# rat.net
KiCad netlist of a schematic drawn in EAGLE
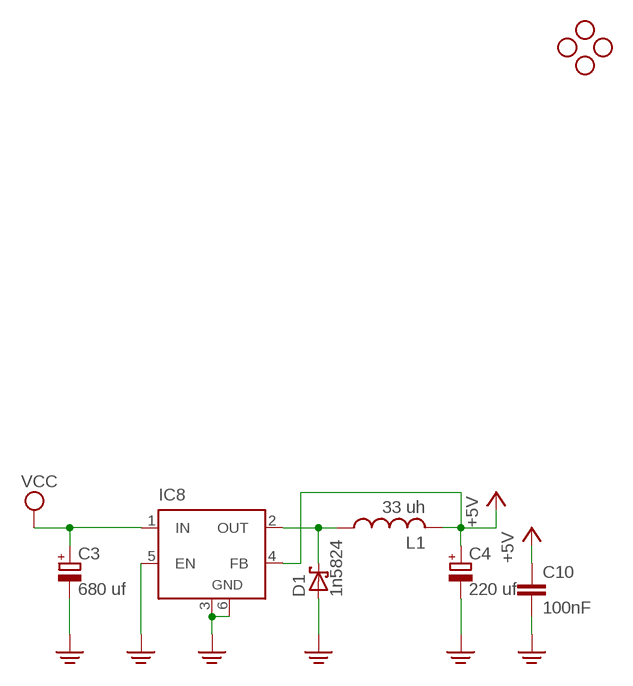
[diagram p0: schematic, sheet 1, part 1 of 2]
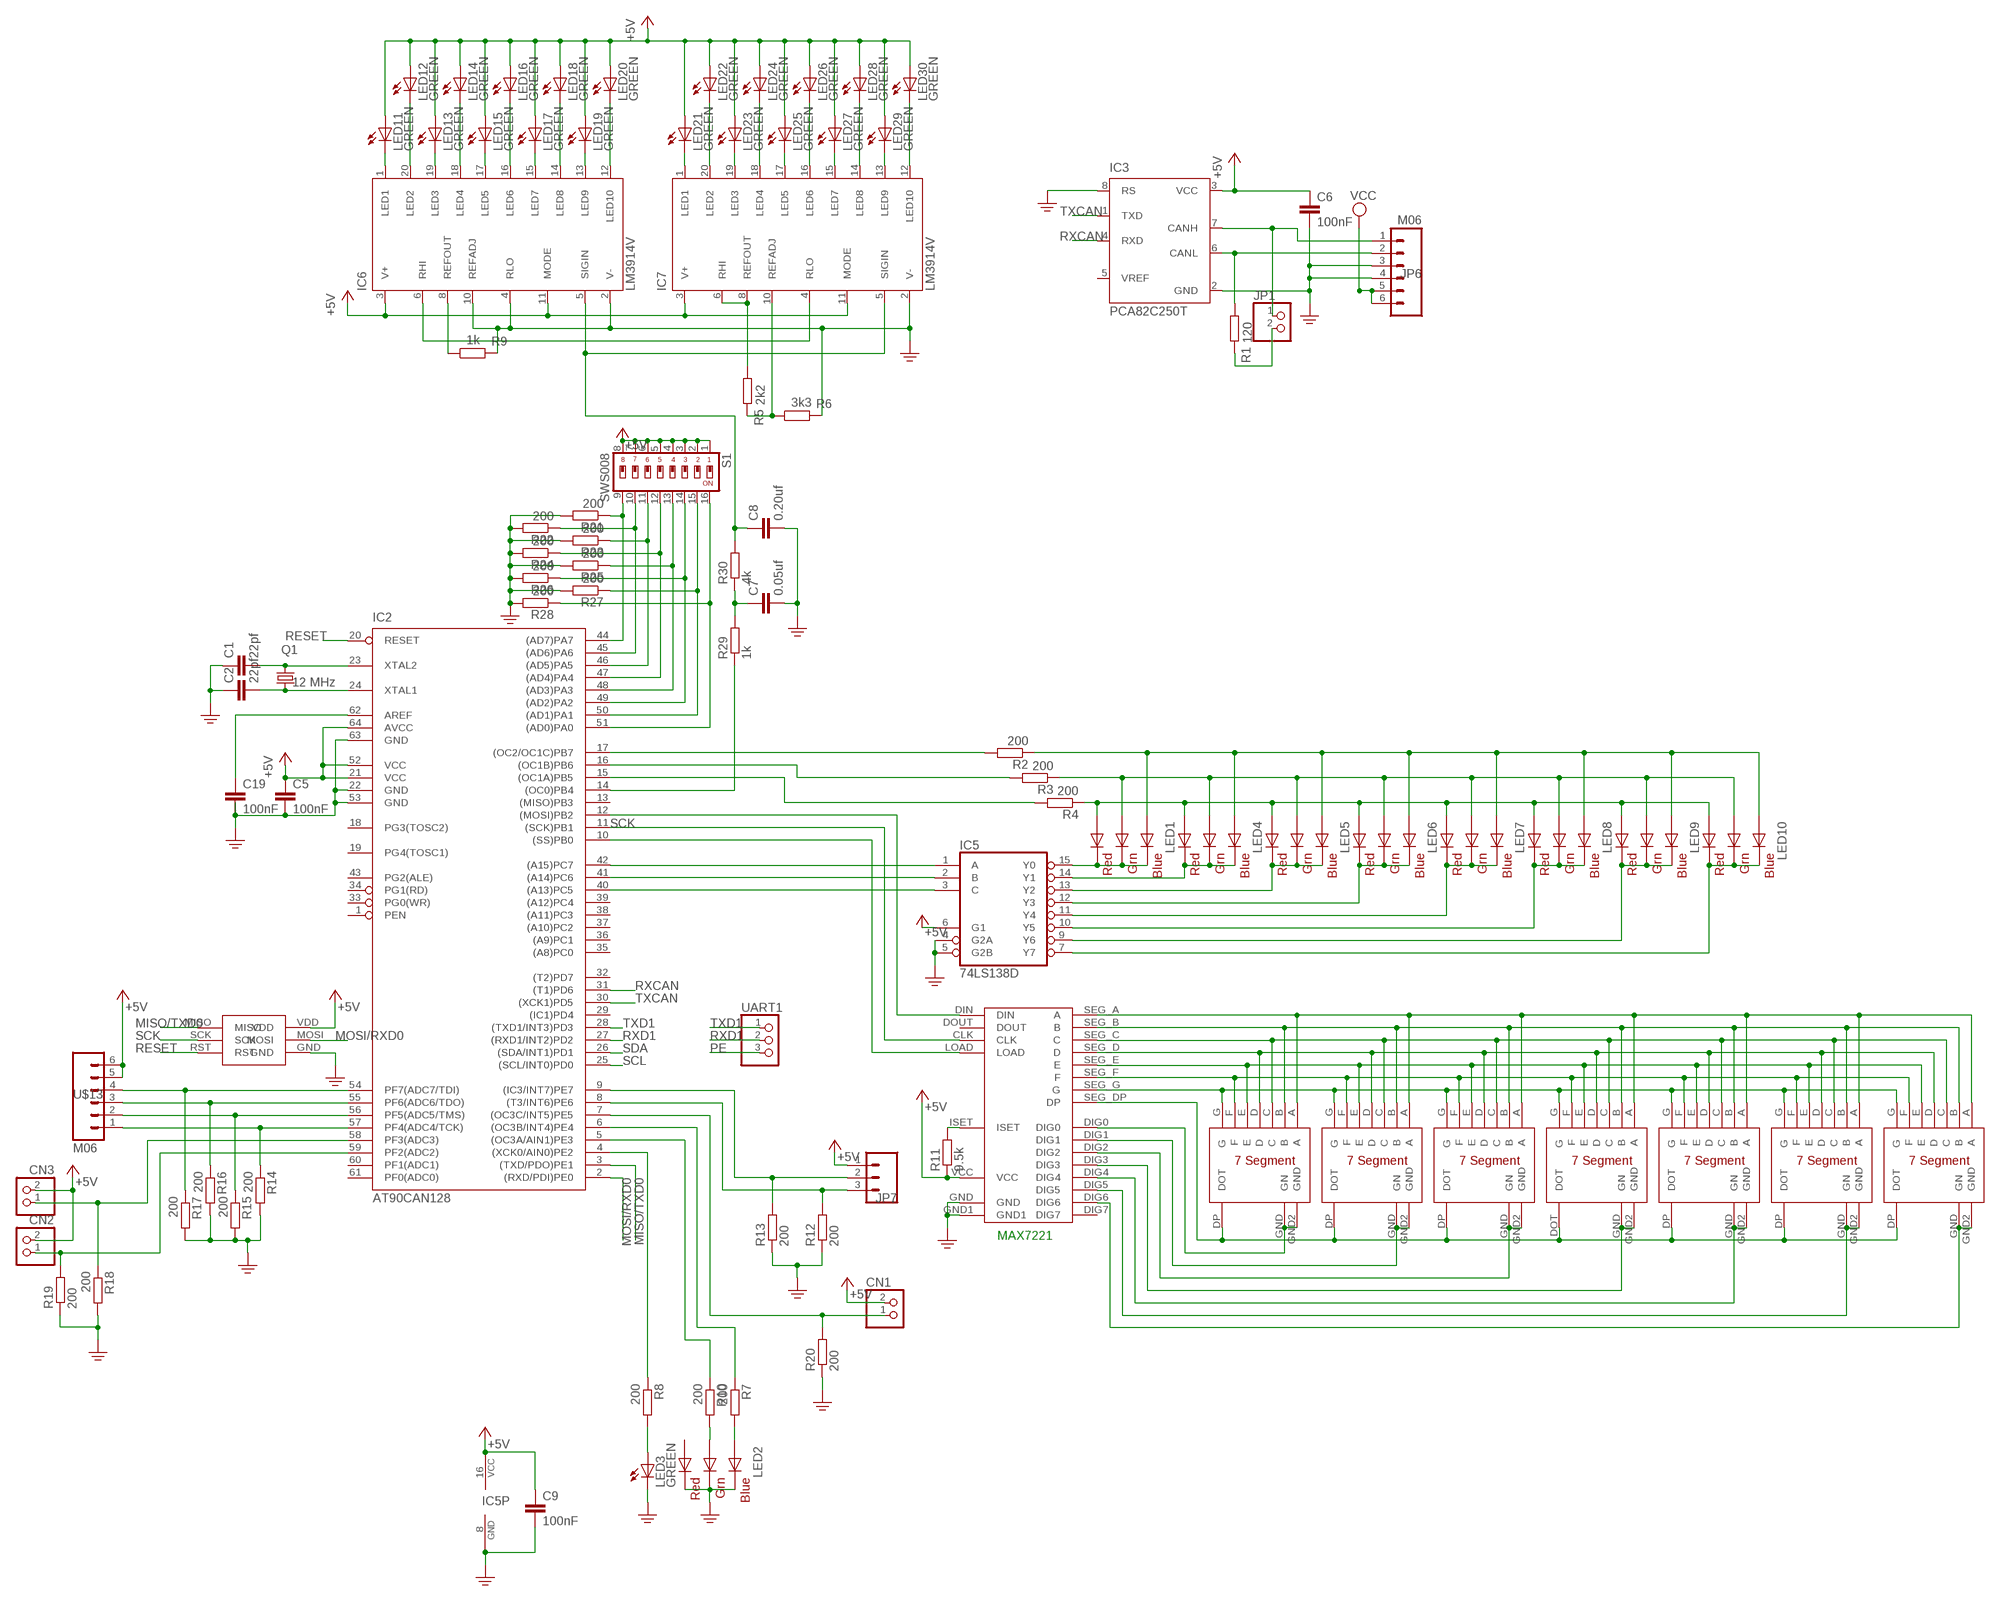
[diagram p1: schematic, sheet 1, part 2 of 2]

(export (version "E")
  (design (tool "Eeschema 10.0.6"))
  (components
    (comp (ref "C1")
      (value "22pf")
      (footprint "eagle-import:C0603K")
      (libsource (lib "eagle-import") (part "C-EUC0603K"))
    )
    (comp (ref "C2")
      (value "22pf")
      (footprint "eagle-import:C0603K")
      (libsource (lib "eagle-import") (part "C-EUC0603K"))
    )
    (comp (ref "C3")
      (value "680 uf")
      (footprint "eagle-import:E5-10,5")
      (libsource (lib "eagle-import") (part "CPOL-EUE5-10.5"))
    )
    (comp (ref "C4")
      (value "220 uf")
      (footprint "eagle-import:E2,5-7")
      (libsource (lib "eagle-import") (part "CPOL-EUE2.5-7"))
    )
    (comp (ref "C5")
      (value "100nF")
      (footprint "eagle-import:C0603K")
      (libsource (lib "eagle-import") (part "C-EUC0603K"))
    )
    (comp (ref "C6")
      (value "100nF")
      (footprint "eagle-import:C0603K")
      (libsource (lib "eagle-import") (part "C-EUC0603K"))
    )
    (comp (ref "C7")
      (value "0.05uf")
      (footprint "eagle-import:C0603K")
      (libsource (lib "eagle-import") (part "C-EUC0603K"))
    )
    (comp (ref "C8")
      (value "0.20uf")
      (footprint "eagle-import:C0603K")
      (libsource (lib "eagle-import") (part "C-EUC0603K"))
    )
    (comp (ref "C9")
      (value "100nF")
      (footprint "eagle-import:C0603K")
      (libsource (lib "eagle-import") (part "C-EUC0603K"))
    )
    (comp (ref "C10")
      (value "100nF")
      (footprint "eagle-import:C0603K")
      (libsource (lib "eagle-import") (part "C-EUC0603K"))
    )
    (comp (ref "C19")
      (value "100nF")
      (footprint "eagle-import:C0603K")
      (libsource (lib "eagle-import") (part "C-EUC0603K"))
    )
    (comp (ref "CN1")
      (value "JST_2PIN-SMT-RA")
      (footprint "eagle-import:JST-PH-2-SMT-RA")
      (libsource (lib "eagle-import") (part "JST_2PIN-SMT-RA"))
    )
    (comp (ref "CN2")
      (value "JST_2PIN-SMT-RA")
      (footprint "eagle-import:JST-PH-2-SMT-RA")
      (libsource (lib "eagle-import") (part "JST_2PIN-SMT-RA"))
    )
    (comp (ref "CN3")
      (value "JST_2PIN-SMT-RA")
      (footprint "eagle-import:JST-PH-2-SMT-RA")
      (libsource (lib "eagle-import") (part "JST_2PIN-SMT-RA"))
    )
    (comp (ref "D1")
      (value "1n5824")
      (footprint "eagle-import:P6T15")
      (libsource (lib "eagle-import") (part "SCHOTTKY-DIODEP6T15"))
    )
    (comp (ref "IC2")
      (value "AT90CAN128")
      (footprint "eagle-import:TQFP64")
      (fields (field (name "MPN") "ATMEGA128-16AU"))
      (libsource (lib "eagle-import") (part "MEGA128-A"))
    )
    (comp (ref "IC3")
      (value "PCA82C250T")
      (footprint "eagle-import:SO8")
      (libsource (lib "eagle-import") (part "PCA82C250T"))
    )
    (comp (ref "IC5")
      (value "74LS138D")
      (footprint "eagle-import:SO16")
      (libsource (lib "eagle-import") (part "74138DLS"))
    )
    (comp (ref "IC6")
      (value "LM3914V")
      (footprint "eagle-import:PLCC20S")
      (libsource (lib "eagle-import") (part "LM391V4"))
    )
    (comp (ref "IC7")
      (value "LM3914V")
      (footprint "eagle-import:PLCC20S")
      (libsource (lib "eagle-import") (part "LM391V4"))
    )
    (comp (ref "IC8")
      (value "LM2596S")
      (footprint "eagle-import:TO263-5")
      (libsource (lib "eagle-import") (part "LM2596S"))
    )
    (comp (ref "JP1")
      (value "PINHD-1X2")
      (footprint "eagle-import:1X02")
      (libsource (lib "eagle-import") (part "PINHD-1X2"))
    )
    (comp (ref "JP2")
      (value "STAND-OFF")
      (footprint "eagle-import:STAND-OFF")
      (libsource (lib "eagle-import") (part "STAND-OFF"))
    )
    (comp (ref "JP3")
      (value "STAND-OFF")
      (footprint "eagle-import:STAND-OFF")
      (libsource (lib "eagle-import") (part "STAND-OFF"))
    )
    (comp (ref "JP4")
      (value "STAND-OFF")
      (footprint "eagle-import:STAND-OFF")
      (libsource (lib "eagle-import") (part "STAND-OFF"))
    )
    (comp (ref "JP5")
      (value "STAND-OFF")
      (footprint "eagle-import:STAND-OFF")
      (libsource (lib "eagle-import") (part "STAND-OFF"))
    )
    (comp (ref "JP6")
      (value "M06")
      (footprint "eagle-import:S6B_PH")
      (libsource (lib "eagle-import") (part "M06"))
    )
    (comp (ref "JP7")
      (value "M03")
      (footprint "eagle-import:S3B-PH")
      (libsource (lib "eagle-import") (part "M03"))
    )
    (comp (ref "L1")
      (value "33 uh")
      (footprint "eagle-import:TFI0410")
      (libsource (lib "eagle-import") (part "L-USTFI0410"))
    )
    (comp (ref "LED1")
      (value "RGBLED5050")
      (footprint "eagle-import:RGBLED5050")
      (libsource (lib "eagle-import") (part "RGBLED5050"))
    )
    (comp (ref "LED2")
      (value "RGBLED5050")
      (footprint "eagle-import:RGBLED5050")
      (libsource (lib "eagle-import") (part "RGBLED5050"))
    )
    (comp (ref "LED3")
      (value "GREEN")
      (footprint "eagle-import:1206")
      (libsource (lib "eagle-import") (part "LEDSMT1206"))
    )
    (comp (ref "LED4")
      (value "RGBLED5050")
      (footprint "eagle-import:RGBLED5050")
      (libsource (lib "eagle-import") (part "RGBLED5050"))
    )
    (comp (ref "LED5")
      (value "RGBLED5050")
      (footprint "eagle-import:RGBLED5050")
      (libsource (lib "eagle-import") (part "RGBLED5050"))
    )
    (comp (ref "LED6")
      (value "RGBLED5050")
      (footprint "eagle-import:RGBLED5050")
      (libsource (lib "eagle-import") (part "RGBLED5050"))
    )
    (comp (ref "LED7")
      (value "RGBLED5050")
      (footprint "eagle-import:RGBLED5050")
      (libsource (lib "eagle-import") (part "RGBLED5050"))
    )
    (comp (ref "LED8")
      (value "RGBLED5050")
      (footprint "eagle-import:RGBLED5050")
      (libsource (lib "eagle-import") (part "RGBLED5050"))
    )
    (comp (ref "LED9")
      (value "RGBLED5050")
      (footprint "eagle-import:RGBLED5050")
      (libsource (lib "eagle-import") (part "RGBLED5050"))
    )
    (comp (ref "LED10")
      (value "RGBLED5050")
      (footprint "eagle-import:RGBLED5050")
      (libsource (lib "eagle-import") (part "RGBLED5050"))
    )
    (comp (ref "LED11")
      (value "GREEN")
      (footprint "eagle-import:1206")
      (libsource (lib "eagle-import") (part "LEDSMT1206"))
    )
    (comp (ref "LED12")
      (value "GREEN")
      (footprint "eagle-import:1206")
      (libsource (lib "eagle-import") (part "LEDSMT1206"))
    )
    (comp (ref "LED13")
      (value "GREEN")
      (footprint "eagle-import:1206")
      (libsource (lib "eagle-import") (part "LEDSMT1206"))
    )
    (comp (ref "LED14")
      (value "GREEN")
      (footprint "eagle-import:1206")
      (libsource (lib "eagle-import") (part "LEDSMT1206"))
    )
    (comp (ref "LED15")
      (value "GREEN")
      (footprint "eagle-import:1206")
      (libsource (lib "eagle-import") (part "LEDSMT1206"))
    )
    (comp (ref "LED16")
      (value "GREEN")
      (footprint "eagle-import:1206")
      (libsource (lib "eagle-import") (part "LEDSMT1206"))
    )
    (comp (ref "LED17")
      (value "GREEN")
      (footprint "eagle-import:1206")
      (libsource (lib "eagle-import") (part "LEDSMT1206"))
    )
    (comp (ref "LED18")
      (value "GREEN")
      (footprint "eagle-import:1206")
      (libsource (lib "eagle-import") (part "LEDSMT1206"))
    )
    (comp (ref "LED19")
      (value "GREEN")
      (footprint "eagle-import:1206")
      (libsource (lib "eagle-import") (part "LEDSMT1206"))
    )
    (comp (ref "LED20")
      (value "GREEN")
      (footprint "eagle-import:1206")
      (libsource (lib "eagle-import") (part "LEDSMT1206"))
    )
    (comp (ref "LED21")
      (value "GREEN")
      (footprint "eagle-import:1206")
      (libsource (lib "eagle-import") (part "LEDSMT1206"))
    )
    (comp (ref "LED22")
      (value "GREEN")
      (footprint "eagle-import:1206")
      (libsource (lib "eagle-import") (part "LEDSMT1206"))
    )
    (comp (ref "LED23")
      (value "GREEN")
      (footprint "eagle-import:1206")
      (libsource (lib "eagle-import") (part "LEDSMT1206"))
    )
    (comp (ref "LED24")
      (value "GREEN")
      (footprint "eagle-import:1206")
      (libsource (lib "eagle-import") (part "LEDSMT1206"))
    )
    (comp (ref "LED25")
      (value "GREEN")
      (footprint "eagle-import:1206")
      (libsource (lib "eagle-import") (part "LEDSMT1206"))
    )
    (comp (ref "LED26")
      (value "GREEN")
      (footprint "eagle-import:1206")
      (libsource (lib "eagle-import") (part "LEDSMT1206"))
    )
    (comp (ref "LED27")
      (value "GREEN")
      (footprint "eagle-import:1206")
      (libsource (lib "eagle-import") (part "LEDSMT1206"))
    )
    (comp (ref "LED28")
      (value "GREEN")
      (footprint "eagle-import:1206")
      (libsource (lib "eagle-import") (part "LEDSMT1206"))
    )
    (comp (ref "LED29")
      (value "GREEN")
      (footprint "eagle-import:1206")
      (libsource (lib "eagle-import") (part "LEDSMT1206"))
    )
    (comp (ref "LED30")
      (value "GREEN")
      (footprint "eagle-import:1206")
      (libsource (lib "eagle-import") (part "LEDSMT1206"))
    )
    (comp (ref "Q1")
      (value "12 MHz")
      (footprint "eagle-import:HC49U70")
      (libsource (lib "eagle-import") (part "CRYSTALHC49U70"))
    )
    (comp (ref "R1")
      (value "120")
      (footprint "eagle-import:R0603")
      (libsource (lib "eagle-import") (part "resistor_R-EU_R0603"))
    )
    (comp (ref "R2")
      (value "200")
      (footprint "eagle-import:R0603")
      (libsource (lib "eagle-import") (part "R-EU_R0603"))
    )
    (comp (ref "R3")
      (value "200")
      (footprint "eagle-import:R0603")
      (libsource (lib "eagle-import") (part "R-EU_R0603"))
    )
    (comp (ref "R4")
      (value "200")
      (footprint "eagle-import:R0603")
      (libsource (lib "eagle-import") (part "R-EU_R0603"))
    )
    (comp (ref "R5")
      (value "2k2")
      (footprint "eagle-import:R0603")
      (libsource (lib "eagle-import") (part "resistor_R-EU_R0603"))
    )
    (comp (ref "R6")
      (value "3k3")
      (footprint "eagle-import:R0603")
      (libsource (lib "eagle-import") (part "resistor_R-EU_R0603"))
    )
    (comp (ref "R7")
      (value "200")
      (footprint "eagle-import:R0603")
      (libsource (lib "eagle-import") (part "R-EU_R0603"))
    )
    (comp (ref "R8")
      (value "200")
      (footprint "eagle-import:R0603")
      (libsource (lib "eagle-import") (part "R-EU_R0603"))
    )
    (comp (ref "R9")
      (value "1k")
      (footprint "eagle-import:R0603")
      (libsource (lib "eagle-import") (part "resistor_R-EU_R0603"))
    )
    (comp (ref "R10")
      (value "200")
      (footprint "eagle-import:R0603")
      (libsource (lib "eagle-import") (part "R-EU_R0603"))
    )
    (comp (ref "R11")
      (value "9.5k")
      (footprint "eagle-import:R0603")
      (libsource (lib "eagle-import") (part "R-EU_R0603"))
    )
    (comp (ref "R12")
      (value "200")
      (footprint "eagle-import:R0603")
      (libsource (lib "eagle-import") (part "R-EU_R0603"))
    )
    (comp (ref "R13")
      (value "200")
      (footprint "eagle-import:R0603")
      (libsource (lib "eagle-import") (part "R-EU_R0603"))
    )
    (comp (ref "R14")
      (value "200")
      (footprint "eagle-import:R0603")
      (libsource (lib "eagle-import") (part "R-EU_R0603"))
    )
    (comp (ref "R15")
      (value "200")
      (footprint "eagle-import:R0603")
      (libsource (lib "eagle-import") (part "R-EU_R0603"))
    )
    (comp (ref "R16")
      (value "200")
      (footprint "eagle-import:R0603")
      (libsource (lib "eagle-import") (part "R-EU_R0603"))
    )
    (comp (ref "R17")
      (value "200")
      (footprint "eagle-import:R0603")
      (libsource (lib "eagle-import") (part "R-EU_R0603"))
    )
    (comp (ref "R18")
      (value "200")
      (footprint "eagle-import:R0603")
      (libsource (lib "eagle-import") (part "R-EU_R0603"))
    )
    (comp (ref "R19")
      (value "200")
      (footprint "eagle-import:R0603")
      (libsource (lib "eagle-import") (part "R-EU_R0603"))
    )
    (comp (ref "R20")
      (value "200")
      (footprint "eagle-import:R0603")
      (libsource (lib "eagle-import") (part "R-EU_R0603"))
    )
    (comp (ref "R21")
      (value "200")
      (footprint "eagle-import:R0603")
      (libsource (lib "eagle-import") (part "R-EU_R0603"))
    )
    (comp (ref "R22")
      (value "200")
      (footprint "eagle-import:R0603")
      (libsource (lib "eagle-import") (part "R-EU_R0603"))
    )
    (comp (ref "R23")
      (value "200")
      (footprint "eagle-import:R0603")
      (libsource (lib "eagle-import") (part "R-EU_R0603"))
    )
    (comp (ref "R24")
      (value "200")
      (footprint "eagle-import:R0603")
      (libsource (lib "eagle-import") (part "R-EU_R0603"))
    )
    (comp (ref "R25")
      (value "200")
      (footprint "eagle-import:R0603")
      (libsource (lib "eagle-import") (part "R-EU_R0603"))
    )
    (comp (ref "R26")
      (value "200")
      (footprint "eagle-import:R0603")
      (libsource (lib "eagle-import") (part "R-EU_R0603"))
    )
    (comp (ref "R27")
      (value "200")
      (footprint "eagle-import:R0603")
      (libsource (lib "eagle-import") (part "R-EU_R0603"))
    )
    (comp (ref "R28")
      (value "200")
      (footprint "eagle-import:R0603")
      (libsource (lib "eagle-import") (part "R-EU_R0603"))
    )
    (comp (ref "R29")
      (value "1k")
      (footprint "eagle-import:R0603")
      (libsource (lib "eagle-import") (part "R-EU_R0603"))
    )
    (comp (ref "R30")
      (value "4k")
      (footprint "eagle-import:R0603")
      (libsource (lib "eagle-import") (part "R-EU_R0603"))
    )
    (comp (ref "S1")
      (value "SWS008")
      (footprint "eagle-import:SMS-008")
      (libsource (lib "eagle-import") (part "SWS008"))
    )
    (comp (ref "U$2")
      (value "REDSEVENSEGMENT")
      (footprint "eagle-import:REDSEGMENT")
      (libsource (lib "eagle-import") (part "REDSEVENSEGMENT"))
    )
    (comp (ref "U$3")
      (value "REDSEVENSEGMENT")
      (footprint "eagle-import:REDSEGMENT")
      (libsource (lib "eagle-import") (part "REDSEVENSEGMENT"))
    )
    (comp (ref "U$4")
      (value "REDSEVENSEGMENT")
      (footprint "eagle-import:REDSEGMENT")
      (libsource (lib "eagle-import") (part "REDSEVENSEGMENT"))
    )
    (comp (ref "U$5")
      (value "BIGSEVENSEGMENT")
      (footprint "eagle-import:BIGSEVENSEGMENT")
      (libsource (lib "eagle-import") (part "BIGSEVENSEGMENT"))
    )
    (comp (ref "U$6")
      (value "REDSEVENSEGMENT")
      (footprint "eagle-import:REDSEGMENT")
      (libsource (lib "eagle-import") (part "REDSEVENSEGMENT"))
    )
    (comp (ref "U$7")
      (value "REDSEVENSEGMENT")
      (footprint "eagle-import:REDSEGMENT")
      (libsource (lib "eagle-import") (part "REDSEVENSEGMENT"))
    )
    (comp (ref "U$8")
      (value "REDSEVENSEGMENT")
      (footprint "eagle-import:REDSEGMENT")
      (libsource (lib "eagle-import") (part "REDSEVENSEGMENT"))
    )
    (comp (ref "U$9")
      (value "ISP-HEADER")
      (footprint "eagle-import:ISP-HEADER")
      (libsource (lib "eagle-import") (part "ISP-HEADER"))
    )
    (comp (ref "U$13")
      (value "M06")
      (footprint "eagle-import:S6B_PH")
      (libsource (lib "eagle-import") (part "M06"))
    )
    (comp (ref "U$14")
      (value "MAX7221-SMD")
      (footprint "eagle-import:MAX7221")
      (libsource (lib "eagle-import") (part "MAX7221-SMD"))
    )
    (comp (ref "UART1")
      (value "PINHD-1X3")
      (footprint "eagle-import:1X03")
      (libsource (lib "eagle-import") (part "PINHD-1X3"))
    )
  )
  (nets
    (net (code "1") (name "+5V") (class "Default")
      (node (ref "C10") (pin "1") (pinfunction "1_1") (pintype "passive"))
      (node (ref "C4") (pin "+") (pinfunction "+_+") (pintype "passive"))
      (node (ref "C5") (pin "1") (pinfunction "1_1") (pintype "passive"))
      (node (ref "C6") (pin "1") (pinfunction "1_1") (pintype "passive"))
      (node (ref "C9") (pin "1") (pinfunction "1_1") (pintype "passive"))
      (node (ref "CN1") (pin "2") (pinfunction "1_2") (pintype "passive"))
      (node (ref "CN2") (pin "2") (pinfunction "1_2") (pintype "passive"))
      (node (ref "CN3") (pin "2") (pinfunction "1_2") (pintype "passive"))
      (node (ref "IC2") (pin "21") (pinfunction "VCC_21") (pintype "power_in"))
      (node (ref "IC2") (pin "52") (pinfunction "VCC_52") (pintype "power_in"))
      (node (ref "IC2") (pin "64") (pinfunction "AVCC_64") (pintype "power_in"))
      (node (ref "IC3") (pin "3") (pinfunction "VCC_3") (pintype "power_in"))
      (node (ref "IC5") (pin "16") (pinfunction "VCC_16") (pintype "power_in"))
      (node (ref "IC5") (pin "6") (pinfunction "G1_6") (pintype "input"))
      (node (ref "IC6") (pin "11") (pinfunction "MODE_11") (pintype "input"))
      (node (ref "IC6") (pin "3") (pinfunction "V+_3") (pintype "power_in"))
      (node (ref "IC7") (pin "11") (pinfunction "MODE_11") (pintype "input"))
      (node (ref "IC7") (pin "3") (pinfunction "V+_3") (pintype "power_in"))
      (node (ref "IC8") (pin "4") (pinfunction "FB_4") (pintype "input"))
      (node (ref "JP7") (pin "1") (pinfunction "1_1") (pintype "passive"))
      (node (ref "L1") (pin "2") (pinfunction "2_2") (pintype "passive"))
      (node (ref "LED11") (pin "A") (pinfunction "A_A") (pintype "passive"))
      (node (ref "LED12") (pin "A") (pinfunction "A_A") (pintype "passive"))
      (node (ref "LED13") (pin "A") (pinfunction "A_A") (pintype "passive"))
      (node (ref "LED14") (pin "A") (pinfunction "A_A") (pintype "passive"))
      (node (ref "LED15") (pin "A") (pinfunction "A_A") (pintype "passive"))
      (node (ref "LED16") (pin "A") (pinfunction "A_A") (pintype "passive"))
      (node (ref "LED17") (pin "A") (pinfunction "A_A") (pintype "passive"))
      (node (ref "LED18") (pin "A") (pinfunction "A_A") (pintype "passive"))
      (node (ref "LED19") (pin "A") (pinfunction "A_A") (pintype "passive"))
      (node (ref "LED20") (pin "A") (pinfunction "A_A") (pintype "passive"))
      (node (ref "LED21") (pin "A") (pinfunction "A_A") (pintype "passive"))
      (node (ref "LED22") (pin "A") (pinfunction "A_A") (pintype "passive"))
      (node (ref "LED23") (pin "A") (pinfunction "A_A") (pintype "passive"))
      (node (ref "LED24") (pin "A") (pinfunction "A_A") (pintype "passive"))
      (node (ref "LED25") (pin "A") (pinfunction "A_A") (pintype "passive"))
      (node (ref "LED26") (pin "A") (pinfunction "A_A") (pintype "passive"))
      (node (ref "LED27") (pin "A") (pinfunction "A_A") (pintype "passive"))
      (node (ref "LED28") (pin "A") (pinfunction "A_A") (pintype "passive"))
      (node (ref "LED29") (pin "A") (pinfunction "A_A") (pintype "passive"))
      (node (ref "LED30") (pin "A") (pinfunction "A_A") (pintype "passive"))
      (node (ref "R11") (pin "1") (pinfunction "1_1") (pintype "passive"))
      (node (ref "S1") (pin "1") (pinfunction "1_1") (pintype "passive"))
      (node (ref "S1") (pin "2") (pinfunction "2_2") (pintype "passive"))
      (node (ref "S1") (pin "3") (pinfunction "3_3") (pintype "passive"))
      (node (ref "S1") (pin "4") (pinfunction "4_4") (pintype "passive"))
      (node (ref "S1") (pin "5") (pinfunction "5_5") (pintype "passive"))
      (node (ref "S1") (pin "6") (pinfunction "6_6") (pintype "passive"))
      (node (ref "S1") (pin "7") (pinfunction "7_7") (pintype "passive"))
      (node (ref "S1") (pin "8") (pinfunction "8_8") (pintype "passive"))
      (node (ref "U$13") (pin "5") (pinfunction "5_5") (pintype "passive"))
      (node (ref "U$13") (pin "6") (pinfunction "6_6") (pintype "passive"))
      (node (ref "U$14") (pin "VCC") (pinfunction "VCC_VCC") (pintype "bidirectional"))
      (node (ref "U$9") (pin "VDD") (pinfunction "VDD_VDD") (pintype "bidirectional"))
    )
    (net (code "2") (name "/MISO{slash}TXD0") (class "Default")
      (node (ref "IC2") (pin "3") (pinfunction "(TXD/PDO)PE1_3") (pintype "bidirectional"))
      (node (ref "U$9") (pin "MISO") (pinfunction "MISO_MISO") (pintype "bidirectional"))
    )
    (net (code "3") (name "/MOSI{slash}RXD0") (class "Default")
      (node (ref "IC2") (pin "2") (pinfunction "(RXD/PDI)PE0_2") (pintype "bidirectional"))
      (node (ref "U$9") (pin "MOSI") (pinfunction "MOSI_MOSI") (pintype "bidirectional"))
    )
    (net (code "4") (name "/RESET") (class "Default")
      (node (ref "IC2") (pin "20") (pinfunction "RESET_20") (pintype "input"))
      (node (ref "U$9") (pin "RST") (pinfunction "RST_RST") (pintype "bidirectional"))
    )
    (net (code "5") (name "/RXCAN") (class "Default")
      (node (ref "IC2") (pin "31") (pinfunction "(T1)PD6_31") (pintype "bidirectional"))
      (node (ref "IC3") (pin "4") (pinfunction "RXD_4") (pintype "output"))
    )
    (net (code "6") (name "/RXD1") (class "Default")
      (node (ref "IC2") (pin "27") (pinfunction "(RXD1/INT2)PD2_27") (pintype "bidirectional"))
      (node (ref "UART1") (pin "2") (pinfunction "2_2") (pintype "passive"))
    )
    (net (code "7") (name "/SCK") (class "Default")
      (node (ref "IC2") (pin "11") (pinfunction "(SCK)PB1_11") (pintype "bidirectional"))
      (node (ref "U$14") (pin "CLK") (pinfunction "CLK_CLK") (pintype "bidirectional"))
      (node (ref "U$9") (pin "SCK") (pinfunction "SCK_SCK") (pintype "bidirectional"))
    )
    (net (code "8") (name "/SCL") (class "Default")
      (node (ref "IC2") (pin "25") (pinfunction "(SCL/INT0)PD0_25") (pintype "bidirectional"))
    )
    (net (code "9") (name "/SDA") (class "Default")
      (node (ref "IC2") (pin "26") (pinfunction "(SDA/INT1)PD1_26") (pintype "bidirectional"))
    )
    (net (code "10") (name "/TXCAN") (class "Default")
      (node (ref "IC2") (pin "30") (pinfunction "(XCK1)PD5_30") (pintype "bidirectional"))
      (node (ref "IC3") (pin "1") (pinfunction "TXD_1") (pintype "input"))
    )
    (net (code "11") (name "/TXD1") (class "Default")
      (node (ref "IC2") (pin "28") (pinfunction "(TXD1/INT3)PD3_28") (pintype "bidirectional"))
      (node (ref "UART1") (pin "1") (pinfunction "1_1") (pintype "passive"))
    )
    (net (code "12") (name "Net-(C7-Pad1)") (class "Default")
      (node (ref "C7") (pin "1") (pinfunction "1_1") (pintype "passive"))
      (node (ref "R29") (pin "2") (pinfunction "2_2") (pintype "passive"))
      (node (ref "R30") (pin "1") (pinfunction "1_1") (pintype "passive"))
    )
    (net (code "13") (name "Net-(CN1-2)") (class "Default")
      (node (ref "CN1") (pin "1") (pinfunction "2_1") (pintype "passive"))
      (node (ref "IC2") (pin "7") (pinfunction "(OC3C/INT5)PE5_7") (pintype "bidirectional"))
      (node (ref "R20") (pin "2") (pinfunction "2_2") (pintype "passive"))
    )
    (net (code "14") (name "Net-(CN2-2)") (class "Default")
      (node (ref "CN2") (pin "1") (pinfunction "2_1") (pintype "passive"))
      (node (ref "IC2") (pin "59") (pinfunction "PF2(ADC2)_59") (pintype "input"))
      (node (ref "R19") (pin "2") (pinfunction "2_2") (pintype "passive"))
    )
    (net (code "15") (name "Net-(CN3-2)") (class "Default")
      (node (ref "CN3") (pin "1") (pinfunction "2_1") (pintype "passive"))
      (node (ref "IC2") (pin "58") (pinfunction "PF3(ADC3)_58") (pintype "input"))
      (node (ref "R18") (pin "1") (pinfunction "1_1") (pintype "passive"))
    )
    (net (code "16") (name "Net-(IC2-(A13)PC5)") (class "Default")
      (node (ref "IC2") (pin "40") (pinfunction "(A13)PC5_40") (pintype "output"))
      (node (ref "IC5") (pin "3") (pinfunction "C_3") (pintype "input"))
    )
    (net (code "17") (name "Net-(IC2-(A14)PC6)") (class "Default")
      (node (ref "IC2") (pin "41") (pinfunction "(A14)PC6_41") (pintype "output"))
      (node (ref "IC5") (pin "2") (pinfunction "B_2") (pintype "input"))
    )
    (net (code "18") (name "Net-(IC2-(A15)PC7)") (class "Default")
      (node (ref "IC2") (pin "42") (pinfunction "(A15)PC7_42") (pintype "output"))
      (node (ref "IC5") (pin "1") (pinfunction "A_1") (pintype "input"))
    )
    (net (code "19") (name "Net-(IC2-(AD0)PA0)") (class "Default")
      (node (ref "IC2") (pin "51") (pinfunction "(AD0)PA0_51") (pintype "bidirectional"))
      (node (ref "R28") (pin "1") (pinfunction "1_1") (pintype "passive"))
      (node (ref "S1") (pin "16") (pinfunction "16_16") (pintype "passive"))
    )
    (net (code "20") (name "Net-(IC2-(AD1)PA1)") (class "Default")
      (node (ref "IC2") (pin "50") (pinfunction "(AD1)PA1_50") (pintype "bidirectional"))
      (node (ref "R27") (pin "1") (pinfunction "1_1") (pintype "passive"))
      (node (ref "S1") (pin "15") (pinfunction "15_15") (pintype "passive"))
    )
    (net (code "21") (name "Net-(IC2-(AD2)PA2)") (class "Default")
      (node (ref "IC2") (pin "49") (pinfunction "(AD2)PA2_49") (pintype "bidirectional"))
      (node (ref "R26") (pin "1") (pinfunction "1_1") (pintype "passive"))
      (node (ref "S1") (pin "14") (pinfunction "14_14") (pintype "passive"))
    )
    (net (code "22") (name "Net-(IC2-(AD3)PA3)") (class "Default")
      (node (ref "IC2") (pin "48") (pinfunction "(AD3)PA3_48") (pintype "bidirectional"))
      (node (ref "R25") (pin "1") (pinfunction "1_1") (pintype "passive"))
      (node (ref "S1") (pin "13") (pinfunction "13_13") (pintype "passive"))
    )
    (net (code "23") (name "Net-(IC2-(AD4)PA4)") (class "Default")
      (node (ref "IC2") (pin "47") (pinfunction "(AD4)PA4_47") (pintype "bidirectional"))
      (node (ref "R24") (pin "1") (pinfunction "1_1") (pintype "passive"))
      (node (ref "S1") (pin "12") (pinfunction "12_12") (pintype "passive"))
    )
    (net (code "24") (name "Net-(IC2-(AD5)PA5)") (class "Default")
      (node (ref "IC2") (pin "46") (pinfunction "(AD5)PA5_46") (pintype "bidirectional"))
      (node (ref "R23") (pin "1") (pinfunction "1_1") (pintype "passive"))
      (node (ref "S1") (pin "11") (pinfunction "11_11") (pintype "passive"))
    )
    (net (code "25") (name "Net-(IC2-(AD6)PA6)") (class "Default")
      (node (ref "IC2") (pin "45") (pinfunction "(AD6)PA6_45") (pintype "bidirectional"))
      (node (ref "R22") (pin "1") (pinfunction "1_1") (pintype "passive"))
      (node (ref "S1") (pin "10") (pinfunction "10_10") (pintype "passive"))
    )
    (net (code "26") (name "Net-(IC2-(AD7)PA7)") (class "Default")
      (node (ref "IC2") (pin "44") (pinfunction "(AD7)PA7_44") (pintype "bidirectional"))
      (node (ref "R21") (pin "1") (pinfunction "1_1") (pintype "passive"))
      (node (ref "S1") (pin "9") (pinfunction "9_9") (pintype "passive"))
    )
    (net (code "27") (name "Net-(IC2-(IC3{slash}INT7)PE7)") (class "Default")
      (node (ref "IC2") (pin "9") (pinfunction "(IC3/INT7)PE7_9") (pintype "bidirectional"))
      (node (ref "JP7") (pin "2") (pinfunction "2_2") (pintype "passive"))
      (node (ref "R13") (pin "2") (pinfunction "2_2") (pintype "passive"))
    )
    (net (code "28") (name "Net-(IC2-(MOSI)PB2)") (class "Default")
      (node (ref "IC2") (pin "12") (pinfunction "(MOSI)PB2_12") (pintype "bidirectional"))
      (node (ref "U$14") (pin "DIN") (pinfunction "DIN_DIN") (pintype "bidirectional"))
    )
    (net (code "29") (name "Net-(IC2-(OC0)PB4)") (class "Default")
      (node (ref "IC2") (pin "14") (pinfunction "(OC0)PB4_14") (pintype "bidirectional"))
      (node (ref "R29") (pin "1") (pinfunction "1_1") (pintype "passive"))
    )
    (net (code "30") (name "Net-(IC2-(OC1A)PB5)") (class "Default")
      (node (ref "IC2") (pin "15") (pinfunction "(OC1A)PB5_15") (pintype "bidirectional"))
      (node (ref "R4") (pin "2") (pinfunction "2_2") (pintype "passive"))
    )
    (net (code "31") (name "Net-(IC2-(OC1B)PB6)") (class "Default")
      (node (ref "IC2") (pin "16") (pinfunction "(OC1B)PB6_16") (pintype "bidirectional"))
      (node (ref "R3") (pin "2") (pinfunction "2_2") (pintype "passive"))
    )
    (net (code "32") (name "Net-(IC2-(OC2{slash}OC1C)PB7)") (class "Default")
      (node (ref "IC2") (pin "17") (pinfunction "(OC2/OC1C)PB7_17") (pintype "bidirectional"))
      (node (ref "R2") (pin "2") (pinfunction "2_2") (pintype "passive"))
    )
    (net (code "33") (name "Net-(IC2-(OC3A{slash}AIN1)PE3)") (class "Default")
      (node (ref "IC2") (pin "5") (pinfunction "(OC3A/AIN1)PE3_5") (pintype "bidirectional"))
      (node (ref "R10") (pin "1") (pinfunction "1_1") (pintype "passive"))
    )
    (net (code "34") (name "Net-(IC2-(OC3B{slash}INT4)PE4)") (class "Default")
      (node (ref "IC2") (pin "6") (pinfunction "(OC3B/INT4)PE4_6") (pintype "bidirectional"))
      (node (ref "R7") (pin "1") (pinfunction "1_1") (pintype "passive"))
    )
    (net (code "35") (name "Net-(IC2-(SS)PB0)") (class "Default")
      (node (ref "IC2") (pin "10") (pinfunction "(SS)PB0_10") (pintype "bidirectional"))
      (node (ref "U$14") (pin "LOAD") (pinfunction "LOAD_LOAD") (pintype "bidirectional"))
    )
    (net (code "36") (name "Net-(IC2-(T3{slash}INT6)PE6)") (class "Default")
      (node (ref "IC2") (pin "8") (pinfunction "(T3/INT6)PE6_8") (pintype "bidirectional"))
      (node (ref "JP7") (pin "3") (pinfunction "3_3") (pintype "passive"))
      (node (ref "R12") (pin "2") (pinfunction "2_2") (pintype "passive"))
    )
    (net (code "37") (name "Net-(IC2-(XCK0{slash}AIN0)PE2)") (class "Default")
      (node (ref "IC2") (pin "4") (pinfunction "(XCK0/AIN0)PE2_4") (pintype "bidirectional"))
      (node (ref "R8") (pin "1") (pinfunction "1_1") (pintype "passive"))
    )
    (net (code "38") (name "Net-(IC2-AREF)") (class "Default")
      (node (ref "C19") (pin "1") (pinfunction "1_1") (pintype "passive"))
      (node (ref "IC2") (pin "62") (pinfunction "AREF_62") (pintype "passive"))
    )
    (net (code "39") (name "Net-(IC2-PF4(ADC4{slash}TCK))") (class "Default")
      (node (ref "IC2") (pin "57") (pinfunction "PF4(ADC4/TCK)_57") (pintype "input"))
      (node (ref "R14") (pin "1") (pinfunction "1_1") (pintype "passive"))
      (node (ref "U$13") (pin "1") (pinfunction "1_1") (pintype "passive"))
    )
    (net (code "40") (name "Net-(IC2-PF5(ADC5{slash}TMS))") (class "Default")
      (node (ref "IC2") (pin "56") (pinfunction "PF5(ADC5/TMS)_56") (pintype "input"))
      (node (ref "R15") (pin "1") (pinfunction "1_1") (pintype "passive"))
      (node (ref "U$13") (pin "2") (pinfunction "2_2") (pintype "passive"))
    )
    (net (code "41") (name "Net-(IC2-PF6(ADC6{slash}TDO))") (class "Default")
      (node (ref "IC2") (pin "55") (pinfunction "PF6(ADC6/TDO)_55") (pintype "input"))
      (node (ref "R16") (pin "1") (pinfunction "1_1") (pintype "passive"))
      (node (ref "U$13") (pin "3") (pinfunction "3_3") (pintype "passive"))
    )
    (net (code "42") (name "Net-(IC2-PF7(ADC7{slash}TDI))") (class "Default")
      (node (ref "IC2") (pin "54") (pinfunction "PF7(ADC7/TDI)_54") (pintype "input"))
      (node (ref "R17") (pin "1") (pinfunction "1_1") (pintype "passive"))
      (node (ref "U$13") (pin "4") (pinfunction "4_4") (pintype "passive"))
    )
    (net (code "43") (name "Net-(IC2-XTAL1)") (class "Default")
      (node (ref "C2") (pin "2") (pinfunction "2_2") (pintype "passive"))
      (node (ref "IC2") (pin "24") (pinfunction "XTAL1_24") (pintype "bidirectional"))
      (node (ref "Q1") (pin "1") (pinfunction "1_1") (pintype "passive"))
    )
    (net (code "44") (name "Net-(IC2-XTAL2)") (class "Default")
      (node (ref "C1") (pin "2") (pinfunction "2_2") (pintype "passive"))
      (node (ref "IC2") (pin "23") (pinfunction "XTAL2_23") (pintype "bidirectional"))
      (node (ref "Q1") (pin "2") (pinfunction "2_2") (pintype "passive"))
    )
    (net (code "45") (name "Net-(IC3-CANH)") (class "Default")
      (node (ref "IC3") (pin "7") (pinfunction "CANH_7") (pintype "bidirectional"))
      (node (ref "JP1") (pin "1") (pinfunction "1_1") (pintype "passive"))
      (node (ref "JP6") (pin "1") (pinfunction "1_1") (pintype "passive"))
    )
    (net (code "46") (name "Net-(IC3-CANL)") (class "Default")
      (node (ref "IC3") (pin "6") (pinfunction "CANL_6") (pintype "bidirectional"))
      (node (ref "JP6") (pin "2") (pinfunction "2_2") (pintype "passive"))
      (node (ref "R1") (pin "1") (pinfunction "1_1") (pintype "passive"))
    )
    (net (code "47") (name "Net-(IC5A-Y0)") (class "Default")
      (node (ref "IC5") (pin "15") (pinfunction "Y0_15") (pintype "output"))
      (node (ref "LED1") (pin "4") (pinfunction "BLUE_C_4") (pintype "bidirectional"))
      (node (ref "LED1") (pin "5") (pinfunction "RED_C_5") (pintype "bidirectional"))
      (node (ref "LED1") (pin "6") (pinfunction "GREEN_C_6") (pintype "bidirectional"))
    )
    (net (code "48") (name "Net-(IC5A-Y1)") (class "Default")
      (node (ref "IC5") (pin "14") (pinfunction "Y1_14") (pintype "output"))
      (node (ref "LED4") (pin "4") (pinfunction "BLUE_C_4") (pintype "bidirectional"))
      (node (ref "LED4") (pin "5") (pinfunction "RED_C_5") (pintype "bidirectional"))
      (node (ref "LED4") (pin "6") (pinfunction "GREEN_C_6") (pintype "bidirectional"))
    )
    (net (code "49") (name "Net-(IC5A-Y2)") (class "Default")
      (node (ref "IC5") (pin "13") (pinfunction "Y2_13") (pintype "output"))
      (node (ref "LED5") (pin "4") (pinfunction "BLUE_C_4") (pintype "bidirectional"))
      (node (ref "LED5") (pin "5") (pinfunction "RED_C_5") (pintype "bidirectional"))
      (node (ref "LED5") (pin "6") (pinfunction "GREEN_C_6") (pintype "bidirectional"))
    )
    (net (code "50") (name "Net-(IC5A-Y3)") (class "Default")
      (node (ref "IC5") (pin "12") (pinfunction "Y3_12") (pintype "output"))
      (node (ref "LED6") (pin "4") (pinfunction "BLUE_C_4") (pintype "bidirectional"))
      (node (ref "LED6") (pin "5") (pinfunction "RED_C_5") (pintype "bidirectional"))
      (node (ref "LED6") (pin "6") (pinfunction "GREEN_C_6") (pintype "bidirectional"))
    )
    (net (code "51") (name "Net-(IC5A-Y4)") (class "Default")
      (node (ref "IC5") (pin "11") (pinfunction "Y4_11") (pintype "output"))
      (node (ref "LED7") (pin "4") (pinfunction "BLUE_C_4") (pintype "bidirectional"))
      (node (ref "LED7") (pin "5") (pinfunction "RED_C_5") (pintype "bidirectional"))
      (node (ref "LED7") (pin "6") (pinfunction "GREEN_C_6") (pintype "bidirectional"))
    )
    (net (code "52") (name "Net-(IC5A-Y5)") (class "Default")
      (node (ref "IC5") (pin "10") (pinfunction "Y5_10") (pintype "output"))
      (node (ref "LED8") (pin "4") (pinfunction "BLUE_C_4") (pintype "bidirectional"))
      (node (ref "LED8") (pin "5") (pinfunction "RED_C_5") (pintype "bidirectional"))
      (node (ref "LED8") (pin "6") (pinfunction "GREEN_C_6") (pintype "bidirectional"))
    )
    (net (code "53") (name "Net-(IC5A-Y6)") (class "Default")
      (node (ref "IC5") (pin "9") (pinfunction "Y6_9") (pintype "output"))
      (node (ref "LED9") (pin "4") (pinfunction "BLUE_C_4") (pintype "bidirectional"))
      (node (ref "LED9") (pin "5") (pinfunction "RED_C_5") (pintype "bidirectional"))
      (node (ref "LED9") (pin "6") (pinfunction "GREEN_C_6") (pintype "bidirectional"))
    )
    (net (code "54") (name "Net-(IC5A-Y7)") (class "Default")
      (node (ref "IC5") (pin "7") (pinfunction "Y7_7") (pintype "output"))
      (node (ref "LED10") (pin "4") (pinfunction "BLUE_C_4") (pintype "bidirectional"))
      (node (ref "LED10") (pin "5") (pinfunction "RED_C_5") (pintype "bidirectional"))
      (node (ref "LED10") (pin "6") (pinfunction "GREEN_C_6") (pintype "bidirectional"))
    )
    (net (code "55") (name "Net-(IC6-LED1)") (class "Default")
      (node (ref "IC6") (pin "1") (pinfunction "LED1_1") (pintype "output"))
      (node (ref "LED11") (pin "C") (pinfunction "C_C") (pintype "passive"))
    )
    (net (code "56") (name "Net-(IC6-LED2)") (class "Default")
      (node (ref "IC6") (pin "20") (pinfunction "LED2_20") (pintype "output"))
      (node (ref "LED12") (pin "C") (pinfunction "C_C") (pintype "passive"))
    )
    (net (code "57") (name "Net-(IC6-LED3)") (class "Default")
      (node (ref "IC6") (pin "19") (pinfunction "LED3_19") (pintype "output"))
      (node (ref "LED13") (pin "C") (pinfunction "C_C") (pintype "passive"))
    )
    (net (code "58") (name "Net-(IC6-LED4)") (class "Default")
      (node (ref "IC6") (pin "18") (pinfunction "LED4_18") (pintype "output"))
      (node (ref "LED14") (pin "C") (pinfunction "C_C") (pintype "passive"))
    )
    (net (code "59") (name "Net-(IC6-LED5)") (class "Default")
      (node (ref "IC6") (pin "17") (pinfunction "LED5_17") (pintype "output"))
      (node (ref "LED15") (pin "C") (pinfunction "C_C") (pintype "passive"))
    )
    (net (code "60") (name "Net-(IC6-LED6)") (class "Default")
      (node (ref "IC6") (pin "16") (pinfunction "LED6_16") (pintype "output"))
      (node (ref "LED16") (pin "C") (pinfunction "C_C") (pintype "passive"))
    )
    (net (code "61") (name "Net-(IC6-LED7)") (class "Default")
      (node (ref "IC6") (pin "15") (pinfunction "LED7_15") (pintype "output"))
      (node (ref "LED17") (pin "C") (pinfunction "C_C") (pintype "passive"))
    )
    (net (code "62") (name "Net-(IC6-LED8)") (class "Default")
      (node (ref "IC6") (pin "14") (pinfunction "LED8_14") (pintype "output"))
      (node (ref "LED18") (pin "C") (pinfunction "C_C") (pintype "passive"))
    )
    (net (code "63") (name "Net-(IC6-LED9)") (class "Default")
      (node (ref "IC6") (pin "13") (pinfunction "LED9_13") (pintype "output"))
      (node (ref "LED19") (pin "C") (pinfunction "C_C") (pintype "passive"))
    )
    (net (code "64") (name "Net-(IC6-LED10)") (class "Default")
      (node (ref "IC6") (pin "12") (pinfunction "LED10_12") (pintype "output"))
      (node (ref "LED20") (pin "C") (pinfunction "C_C") (pintype "passive"))
    )
    (net (code "65") (name "Net-(IC6-REFOUT)") (class "Default")
      (node (ref "IC6") (pin "8") (pinfunction "REFOUT_8") (pintype "output"))
      (node (ref "R9") (pin "1") (pinfunction "1_1") (pintype "passive"))
    )
    (net (code "66") (name "Net-(IC6-RHI)") (class "Default")
      (node (ref "IC6") (pin "6") (pinfunction "RHI_6") (pintype "input"))
      (node (ref "IC7") (pin "4") (pinfunction "RLO_4") (pintype "input"))
    )
    (net (code "67") (name "Net-(IC6-SIGIN)") (class "Default")
      (node (ref "C8") (pin "1") (pinfunction "1_1") (pintype "passive"))
      (node (ref "IC6") (pin "5") (pinfunction "SIGIN_5") (pintype "input"))
      (node (ref "IC7") (pin "5") (pinfunction "SIGIN_5") (pintype "input"))
      (node (ref "R30") (pin "2") (pinfunction "2_2") (pintype "passive"))
    )
    (net (code "68") (name "Net-(IC7-LED1)") (class "Default")
      (node (ref "IC7") (pin "1") (pinfunction "LED1_1") (pintype "output"))
      (node (ref "LED21") (pin "C") (pinfunction "C_C") (pintype "passive"))
    )
    (net (code "69") (name "Net-(IC7-LED2)") (class "Default")
      (node (ref "IC7") (pin "20") (pinfunction "LED2_20") (pintype "output"))
      (node (ref "LED22") (pin "C") (pinfunction "C_C") (pintype "passive"))
    )
    (net (code "70") (name "Net-(IC7-LED3)") (class "Default")
      (node (ref "IC7") (pin "19") (pinfunction "LED3_19") (pintype "output"))
      (node (ref "LED23") (pin "C") (pinfunction "C_C") (pintype "passive"))
    )
    (net (code "71") (name "Net-(IC7-LED4)") (class "Default")
      (node (ref "IC7") (pin "18") (pinfunction "LED4_18") (pintype "output"))
      (node (ref "LED24") (pin "C") (pinfunction "C_C") (pintype "passive"))
    )
    (net (code "72") (name "Net-(IC7-LED5)") (class "Default")
      (node (ref "IC7") (pin "17") (pinfunction "LED5_17") (pintype "output"))
      (node (ref "LED25") (pin "C") (pinfunction "C_C") (pintype "passive"))
    )
    (net (code "73") (name "Net-(IC7-LED6)") (class "Default")
      (node (ref "IC7") (pin "16") (pinfunction "LED6_16") (pintype "output"))
      (node (ref "LED26") (pin "C") (pinfunction "C_C") (pintype "passive"))
    )
    (net (code "74") (name "Net-(IC7-LED7)") (class "Default")
      (node (ref "IC7") (pin "15") (pinfunction "LED7_15") (pintype "output"))
      (node (ref "LED27") (pin "C") (pinfunction "C_C") (pintype "passive"))
    )
    (net (code "75") (name "Net-(IC7-LED8)") (class "Default")
      (node (ref "IC7") (pin "14") (pinfunction "LED8_14") (pintype "output"))
      (node (ref "LED28") (pin "C") (pinfunction "C_C") (pintype "passive"))
    )
    (net (code "76") (name "Net-(IC7-LED9)") (class "Default")
      (node (ref "IC7") (pin "13") (pinfunction "LED9_13") (pintype "output"))
      (node (ref "LED29") (pin "C") (pinfunction "C_C") (pintype "passive"))
    )
    (net (code "77") (name "Net-(IC7-LED10)") (class "Default")
      (node (ref "IC7") (pin "12") (pinfunction "LED10_12") (pintype "output"))
      (node (ref "LED30") (pin "C") (pinfunction "C_C") (pintype "passive"))
    )
    (net (code "78") (name "Net-(IC7-REFADJ)") (class "Default")
      (node (ref "IC7") (pin "10") (pinfunction "REFADJ_10") (pintype "passive"))
      (node (ref "R5") (pin "2") (pinfunction "2_2") (pintype "passive"))
      (node (ref "R6") (pin "1") (pinfunction "1_1") (pintype "passive"))
    )
    (net (code "79") (name "Net-(IC7-REFOUT)") (class "Default")
      (node (ref "IC7") (pin "6") (pinfunction "RHI_6") (pintype "input"))
      (node (ref "IC7") (pin "8") (pinfunction "REFOUT_8") (pintype "output"))
      (node (ref "R5") (pin "1") (pinfunction "1_1") (pintype "passive"))
    )
    (net (code "80") (name "Net-(IC8-OUT)") (class "Default")
      (node (ref "D1") (pin "C") (pinfunction "C_C") (pintype "passive"))
      (node (ref "IC8") (pin "2") (pinfunction "OUT_2") (pintype "output"))
      (node (ref "L1") (pin "1") (pinfunction "1_1") (pintype "passive"))
    )
    (net (code "81") (name "Net-(JP1-Pad2)") (class "Default")
      (node (ref "JP1") (pin "2") (pinfunction "2_2") (pintype "passive"))
      (node (ref "R1") (pin "2") (pinfunction "2_2") (pintype "passive"))
    )
    (net (code "82") (name "Net-(LED1-BLUE_A)") (class "Default")
      (node (ref "LED1") (pin "3") (pinfunction "BLUE_A_3") (pintype "bidirectional"))
      (node (ref "LED10") (pin "3") (pinfunction "BLUE_A_3") (pintype "bidirectional"))
      (node (ref "LED4") (pin "3") (pinfunction "BLUE_A_3") (pintype "bidirectional"))
      (node (ref "LED5") (pin "3") (pinfunction "BLUE_A_3") (pintype "bidirectional"))
      (node (ref "LED6") (pin "3") (pinfunction "BLUE_A_3") (pintype "bidirectional"))
      (node (ref "LED7") (pin "3") (pinfunction "BLUE_A_3") (pintype "bidirectional"))
      (node (ref "LED8") (pin "3") (pinfunction "BLUE_A_3") (pintype "bidirectional"))
      (node (ref "LED9") (pin "3") (pinfunction "BLUE_A_3") (pintype "bidirectional"))
      (node (ref "R2") (pin "1") (pinfunction "1_1") (pintype "passive"))
    )
    (net (code "83") (name "Net-(LED1-GREEN_A)") (class "Default")
      (node (ref "LED1") (pin "1") (pinfunction "GREEN_A_1") (pintype "bidirectional"))
      (node (ref "LED10") (pin "1") (pinfunction "GREEN_A_1") (pintype "bidirectional"))
      (node (ref "LED4") (pin "1") (pinfunction "GREEN_A_1") (pintype "bidirectional"))
      (node (ref "LED5") (pin "1") (pinfunction "GREEN_A_1") (pintype "bidirectional"))
      (node (ref "LED6") (pin "1") (pinfunction "GREEN_A_1") (pintype "bidirectional"))
      (node (ref "LED7") (pin "1") (pinfunction "GREEN_A_1") (pintype "bidirectional"))
      (node (ref "LED8") (pin "1") (pinfunction "GREEN_A_1") (pintype "bidirectional"))
      (node (ref "LED9") (pin "1") (pinfunction "GREEN_A_1") (pintype "bidirectional"))
      (node (ref "R3") (pin "1") (pinfunction "1_1") (pintype "passive"))
    )
    (net (code "84") (name "Net-(LED1-RED_A)") (class "Default")
      (node (ref "LED1") (pin "2") (pinfunction "RED_A_2") (pintype "bidirectional"))
      (node (ref "LED10") (pin "2") (pinfunction "RED_A_2") (pintype "bidirectional"))
      (node (ref "LED4") (pin "2") (pinfunction "RED_A_2") (pintype "bidirectional"))
      (node (ref "LED5") (pin "2") (pinfunction "RED_A_2") (pintype "bidirectional"))
      (node (ref "LED6") (pin "2") (pinfunction "RED_A_2") (pintype "bidirectional"))
      (node (ref "LED7") (pin "2") (pinfunction "RED_A_2") (pintype "bidirectional"))
      (node (ref "LED8") (pin "2") (pinfunction "RED_A_2") (pintype "bidirectional"))
      (node (ref "LED9") (pin "2") (pinfunction "RED_A_2") (pintype "bidirectional"))
      (node (ref "R4") (pin "1") (pinfunction "1_1") (pintype "passive"))
    )
    (net (code "85") (name "Net-(LED2-BLUE_A)") (class "Default")
      (node (ref "LED2") (pin "3") (pinfunction "BLUE_A_3") (pintype "bidirectional"))
      (node (ref "R7") (pin "2") (pinfunction "2_2") (pintype "passive"))
    )
    (net (code "86") (name "Net-(LED2-GREEN_A)") (class "Default")
      (node (ref "LED2") (pin "1") (pinfunction "GREEN_A_1") (pintype "bidirectional"))
      (node (ref "R10") (pin "2") (pinfunction "2_2") (pintype "passive"))
    )
    (net (code "87") (name "Net-(LED3-PadA)") (class "Default")
      (node (ref "LED3") (pin "A") (pinfunction "A_A") (pintype "passive"))
      (node (ref "R8") (pin "2") (pinfunction "2_2") (pintype "passive"))
    )
    (net (code "88") (name "Net-(R11-Pad2)") (class "Default")
      (node (ref "R11") (pin "2") (pinfunction "2_2") (pintype "passive"))
      (node (ref "U$14") (pin "ISET") (pinfunction "ISET_ISET") (pintype "bidirectional"))
    )
    (net (code "89") (name "Net-(U$2-GN)") (class "Default")
      (node (ref "U$14") (pin "DIG0") (pinfunction "DIG0_DIG0") (pintype "bidirectional"))
      (node (ref "U$2") (pin "GND") (pinfunction "GN_GND") (pintype "bidirectional"))
      (node (ref "U$2") (pin "GND2") (pinfunction "GND_GND2") (pintype "bidirectional"))
    )
    (net (code "90") (name "Net-(U$3-GN)") (class "Default")
      (node (ref "U$14") (pin "DIG1") (pinfunction "DIG1_DIG1") (pintype "bidirectional"))
      (node (ref "U$3") (pin "GND") (pinfunction "GN_GND") (pintype "bidirectional"))
      (node (ref "U$3") (pin "GND2") (pinfunction "GND_GND2") (pintype "bidirectional"))
    )
    (net (code "91") (name "Net-(U$4-GN)") (class "Default")
      (node (ref "U$14") (pin "DIG2") (pinfunction "DIG2_DIG2") (pintype "bidirectional"))
      (node (ref "U$4") (pin "GND") (pinfunction "GN_GND") (pintype "bidirectional"))
      (node (ref "U$4") (pin "GND2") (pinfunction "GND_GND2") (pintype "bidirectional"))
    )
    (net (code "92") (name "Net-(U$5-GN)") (class "Default")
      (node (ref "U$14") (pin "DIG3") (pinfunction "DIG3_DIG3") (pintype "bidirectional"))
      (node (ref "U$5") (pin "GND") (pinfunction "GN_GND") (pintype "bidirectional"))
      (node (ref "U$5") (pin "GND2") (pinfunction "GND_GND2") (pintype "bidirectional"))
    )
    (net (code "93") (name "Net-(U$6-GN)") (class "Default")
      (node (ref "U$14") (pin "DIG4") (pinfunction "DIG4_DIG4") (pintype "bidirectional"))
      (node (ref "U$6") (pin "GND") (pinfunction "GN_GND") (pintype "bidirectional"))
      (node (ref "U$6") (pin "GND2") (pinfunction "GND_GND2") (pintype "bidirectional"))
    )
    (net (code "94") (name "Net-(U$7-GN)") (class "Default")
      (node (ref "U$14") (pin "DIG5") (pinfunction "DIG5_DIG5") (pintype "bidirectional"))
      (node (ref "U$7") (pin "GND") (pinfunction "GN_GND") (pintype "bidirectional"))
      (node (ref "U$7") (pin "GND2") (pinfunction "GND_GND2") (pintype "bidirectional"))
    )
    (net (code "95") (name "Net-(U$8-GN)") (class "Default")
      (node (ref "U$14") (pin "DIG6") (pinfunction "DIG6_DIG6") (pintype "bidirectional"))
      (node (ref "U$8") (pin "GND") (pinfunction "GN_GND") (pintype "bidirectional"))
      (node (ref "U$8") (pin "GND2") (pinfunction "GND_GND2") (pintype "bidirectional"))
    )
    (net (code "96") (name "Net-(U$14-A)") (class "Default")
      (node (ref "U$14") (pin "SEG_A") (pinfunction "A_SEG_A") (pintype "bidirectional"))
      (node (ref "U$2") (pin "A") (pinfunction "A_A") (pintype "bidirectional"))
      (node (ref "U$3") (pin "A") (pinfunction "A_A") (pintype "bidirectional"))
      (node (ref "U$4") (pin "A") (pinfunction "A_A") (pintype "bidirectional"))
      (node (ref "U$5") (pin "A") (pinfunction "A_A") (pintype "bidirectional"))
      (node (ref "U$6") (pin "A") (pinfunction "A_A") (pintype "bidirectional"))
      (node (ref "U$7") (pin "A") (pinfunction "A_A") (pintype "bidirectional"))
      (node (ref "U$8") (pin "A") (pinfunction "A_A") (pintype "bidirectional"))
    )
    (net (code "97") (name "Net-(U$14-B)") (class "Default")
      (node (ref "U$14") (pin "SEG_B") (pinfunction "B_SEG_B") (pintype "bidirectional"))
      (node (ref "U$2") (pin "B") (pinfunction "B_B") (pintype "bidirectional"))
      (node (ref "U$3") (pin "B") (pinfunction "B_B") (pintype "bidirectional"))
      (node (ref "U$4") (pin "B") (pinfunction "B_B") (pintype "bidirectional"))
      (node (ref "U$5") (pin "B") (pinfunction "B_B") (pintype "bidirectional"))
      (node (ref "U$6") (pin "B") (pinfunction "B_B") (pintype "bidirectional"))
      (node (ref "U$7") (pin "B") (pinfunction "B_B") (pintype "bidirectional"))
      (node (ref "U$8") (pin "B") (pinfunction "B_B") (pintype "bidirectional"))
    )
    (net (code "98") (name "Net-(U$14-C)") (class "Default")
      (node (ref "U$14") (pin "SEG_C") (pinfunction "C_SEG_C") (pintype "bidirectional"))
      (node (ref "U$2") (pin "C") (pinfunction "C_C") (pintype "bidirectional"))
      (node (ref "U$3") (pin "C") (pinfunction "C_C") (pintype "bidirectional"))
      (node (ref "U$4") (pin "C") (pinfunction "C_C") (pintype "bidirectional"))
      (node (ref "U$5") (pin "C") (pinfunction "C_C") (pintype "bidirectional"))
      (node (ref "U$6") (pin "C") (pinfunction "C_C") (pintype "bidirectional"))
      (node (ref "U$7") (pin "C") (pinfunction "C_C") (pintype "bidirectional"))
      (node (ref "U$8") (pin "C") (pinfunction "C_C") (pintype "bidirectional"))
    )
    (net (code "99") (name "Net-(U$14-D)") (class "Default")
      (node (ref "U$14") (pin "SEG_D") (pinfunction "D_SEG_D") (pintype "bidirectional"))
      (node (ref "U$2") (pin "D") (pinfunction "D_D") (pintype "bidirectional"))
      (node (ref "U$3") (pin "D") (pinfunction "D_D") (pintype "bidirectional"))
      (node (ref "U$4") (pin "D") (pinfunction "D_D") (pintype "bidirectional"))
      (node (ref "U$5") (pin "D") (pinfunction "D_D") (pintype "bidirectional"))
      (node (ref "U$6") (pin "D") (pinfunction "D_D") (pintype "bidirectional"))
      (node (ref "U$7") (pin "D") (pinfunction "D_D") (pintype "bidirectional"))
      (node (ref "U$8") (pin "D") (pinfunction "D_D") (pintype "bidirectional"))
    )
    (net (code "100") (name "Net-(U$14-DP)") (class "Default")
      (node (ref "U$14") (pin "SEG_DP") (pinfunction "DP_SEG_DP") (pintype "bidirectional"))
      (node (ref "U$2") (pin "DP") (pinfunction "DOT_DP") (pintype "bidirectional"))
      (node (ref "U$3") (pin "DP") (pinfunction "DOT_DP") (pintype "bidirectional"))
      (node (ref "U$4") (pin "DP") (pinfunction "DOT_DP") (pintype "bidirectional"))
      (node (ref "U$5") (pin "DOT") (pinfunction "DOT_DOT") (pintype "bidirectional"))
      (node (ref "U$6") (pin "DP") (pinfunction "DOT_DP") (pintype "bidirectional"))
      (node (ref "U$7") (pin "DP") (pinfunction "DOT_DP") (pintype "bidirectional"))
      (node (ref "U$8") (pin "DP") (pinfunction "DOT_DP") (pintype "bidirectional"))
    )
    (net (code "101") (name "Net-(U$14-E)") (class "Default")
      (node (ref "U$14") (pin "SEG_E") (pinfunction "E_SEG_E") (pintype "bidirectional"))
      (node (ref "U$2") (pin "E") (pinfunction "E_E") (pintype "bidirectional"))
      (node (ref "U$3") (pin "E") (pinfunction "E_E") (pintype "bidirectional"))
      (node (ref "U$4") (pin "E") (pinfunction "E_E") (pintype "bidirectional"))
      (node (ref "U$5") (pin "E") (pinfunction "E_E") (pintype "bidirectional"))
      (node (ref "U$6") (pin "E") (pinfunction "E_E") (pintype "bidirectional"))
      (node (ref "U$7") (pin "E") (pinfunction "E_E") (pintype "bidirectional"))
      (node (ref "U$8") (pin "E") (pinfunction "E_E") (pintype "bidirectional"))
    )
    (net (code "102") (name "Net-(U$14-F)") (class "Default")
      (node (ref "U$14") (pin "SEG_F") (pinfunction "F_SEG_F") (pintype "bidirectional"))
      (node (ref "U$2") (pin "F") (pinfunction "F_F") (pintype "bidirectional"))
      (node (ref "U$3") (pin "F") (pinfunction "F_F") (pintype "bidirectional"))
      (node (ref "U$4") (pin "F") (pinfunction "F_F") (pintype "bidirectional"))
      (node (ref "U$5") (pin "F") (pinfunction "F_F") (pintype "bidirectional"))
      (node (ref "U$6") (pin "F") (pinfunction "F_F") (pintype "bidirectional"))
      (node (ref "U$7") (pin "F") (pinfunction "F_F") (pintype "bidirectional"))
      (node (ref "U$8") (pin "F") (pinfunction "F_F") (pintype "bidirectional"))
    )
    (net (code "103") (name "Net-(U$14-G)") (class "Default")
      (node (ref "U$14") (pin "SEG_G") (pinfunction "G_SEG_G") (pintype "bidirectional"))
      (node (ref "U$2") (pin "G") (pinfunction "G_G") (pintype "bidirectional"))
      (node (ref "U$3") (pin "G") (pinfunction "G_G") (pintype "bidirectional"))
      (node (ref "U$4") (pin "G") (pinfunction "G_G") (pintype "bidirectional"))
      (node (ref "U$5") (pin "G") (pinfunction "G_G") (pintype "bidirectional"))
      (node (ref "U$6") (pin "G") (pinfunction "G_G") (pintype "bidirectional"))
      (node (ref "U$7") (pin "G") (pinfunction "G_G") (pintype "bidirectional"))
      (node (ref "U$8") (pin "G") (pinfunction "G_G") (pintype "bidirectional"))
    )
    (net (code "104") (name "PE") (class "Default")
      (node (ref "C1") (pin "1") (pinfunction "1_1") (pintype "passive"))
      (node (ref "C10") (pin "2") (pinfunction "2_2") (pintype "passive"))
      (node (ref "C19") (pin "2") (pinfunction "2_2") (pintype "passive"))
      (node (ref "C2") (pin "1") (pinfunction "1_1") (pintype "passive"))
      (node (ref "C3") (pin "-") (pinfunction "-_-") (pintype "passive"))
      (node (ref "C4") (pin "-") (pinfunction "-_-") (pintype "passive"))
      (node (ref "C5") (pin "2") (pinfunction "2_2") (pintype "passive"))
      (node (ref "C6") (pin "2") (pinfunction "2_2") (pintype "passive"))
      (node (ref "C7") (pin "2") (pinfunction "2_2") (pintype "passive"))
      (node (ref "C8") (pin "2") (pinfunction "2_2") (pintype "passive"))
      (node (ref "C9") (pin "2") (pinfunction "2_2") (pintype "passive"))
      (node (ref "D1") (pin "A") (pinfunction "A_A") (pintype "passive"))
      (node (ref "IC2") (pin "22") (pinfunction "GND_22") (pintype "power_in"))
      (node (ref "IC2") (pin "53") (pinfunction "GND_53") (pintype "power_in"))
      (node (ref "IC2") (pin "63") (pinfunction "GND_63") (pintype "power_in"))
      (node (ref "IC3") (pin "2") (pinfunction "GND_2") (pintype "power_in"))
      (node (ref "IC3") (pin "8") (pinfunction "RS_8") (pintype "input"))
      (node (ref "IC5") (pin "4") (pinfunction "G2A_4") (pintype "input"))
      (node (ref "IC5") (pin "5") (pinfunction "G2B_5") (pintype "input"))
      (node (ref "IC5") (pin "8") (pinfunction "GND_8") (pintype "power_in"))
      (node (ref "IC6") (pin "10") (pinfunction "REFADJ_10") (pintype "passive"))
      (node (ref "IC6") (pin "2") (pinfunction "V-_2") (pintype "power_in"))
      (node (ref "IC6") (pin "4") (pinfunction "RLO_4") (pintype "input"))
      (node (ref "IC7") (pin "2") (pinfunction "V-_2") (pintype "power_in"))
      (node (ref "IC8") (pin "3") (pinfunction "GND_3") (pintype "power_in"))
      (node (ref "IC8") (pin "5") (pinfunction "EN_5") (pintype "input"))
      (node (ref "IC8") (pin "6") (pinfunction "GND_6") (pintype "power_in"))
      (node (ref "JP6") (pin "3") (pinfunction "3_3") (pintype "passive"))
      (node (ref "JP6") (pin "4") (pinfunction "4_4") (pintype "passive"))
      (node (ref "LED2") (pin "4") (pinfunction "BLUE_C_4") (pintype "bidirectional"))
      (node (ref "LED2") (pin "5") (pinfunction "RED_C_5") (pintype "bidirectional"))
      (node (ref "LED2") (pin "6") (pinfunction "GREEN_C_6") (pintype "bidirectional"))
      (node (ref "LED3") (pin "C") (pinfunction "C_C") (pintype "passive"))
      (node (ref "R12") (pin "1") (pinfunction "1_1") (pintype "passive"))
      (node (ref "R13") (pin "1") (pinfunction "1_1") (pintype "passive"))
      (node (ref "R14") (pin "2") (pinfunction "2_2") (pintype "passive"))
      (node (ref "R15") (pin "2") (pinfunction "2_2") (pintype "passive"))
      (node (ref "R16") (pin "2") (pinfunction "2_2") (pintype "passive"))
      (node (ref "R17") (pin "2") (pinfunction "2_2") (pintype "passive"))
      (node (ref "R18") (pin "2") (pinfunction "2_2") (pintype "passive"))
      (node (ref "R19") (pin "1") (pinfunction "1_1") (pintype "passive"))
      (node (ref "R20") (pin "1") (pinfunction "1_1") (pintype "passive"))
      (node (ref "R21") (pin "2") (pinfunction "2_2") (pintype "passive"))
      (node (ref "R22") (pin "2") (pinfunction "2_2") (pintype "passive"))
      (node (ref "R23") (pin "2") (pinfunction "2_2") (pintype "passive"))
      (node (ref "R24") (pin "2") (pinfunction "2_2") (pintype "passive"))
      (node (ref "R25") (pin "2") (pinfunction "2_2") (pintype "passive"))
      (node (ref "R26") (pin "2") (pinfunction "2_2") (pintype "passive"))
      (node (ref "R27") (pin "2") (pinfunction "2_2") (pintype "passive"))
      (node (ref "R28") (pin "2") (pinfunction "2_2") (pintype "passive"))
      (node (ref "R6") (pin "2") (pinfunction "2_2") (pintype "passive"))
      (node (ref "R9") (pin "2") (pinfunction "2_2") (pintype "passive"))
      (node (ref "U$14") (pin "GND") (pinfunction "GND_GND") (pintype "bidirectional"))
      (node (ref "U$14") (pin "GND1") (pinfunction "GND1_GND1") (pintype "bidirectional"))
      (node (ref "U$9") (pin "GND") (pinfunction "GND_GND") (pintype "bidirectional"))
      (node (ref "UART1") (pin "3") (pinfunction "3_3") (pintype "passive"))
    )
    (net (code "105") (name "VCC") (class "Default")
      (node (ref "C3") (pin "+") (pinfunction "+_+") (pintype "passive"))
      (node (ref "IC8") (pin "1") (pinfunction "IN_1") (pintype "input"))
      (node (ref "JP6") (pin "5") (pinfunction "5_5") (pintype "passive"))
      (node (ref "JP6") (pin "6") (pinfunction "6_6") (pintype "passive"))
    )
    (net (code "106") (name "unconnected-(IC2-(A8)PC0-Pad35)") (class "Default")
      (node (ref "IC2") (pin "35") (pinfunction "(A8)PC0_35") (pintype "output"))
    )
    (net (code "107") (name "unconnected-(IC2-(A9)PC1-Pad36)") (class "Default")
      (node (ref "IC2") (pin "36") (pinfunction "(A9)PC1_36") (pintype "output"))
    )
    (net (code "108") (name "unconnected-(IC2-(A10)PC2-Pad37)") (class "Default")
      (node (ref "IC2") (pin "37") (pinfunction "(A10)PC2_37") (pintype "output"))
    )
    (net (code "109") (name "unconnected-(IC2-(A11)PC3-Pad38)") (class "Default")
      (node (ref "IC2") (pin "38") (pinfunction "(A11)PC3_38") (pintype "output"))
    )
    (net (code "110") (name "unconnected-(IC2-(A12)PC4-Pad39)") (class "Default")
      (node (ref "IC2") (pin "39") (pinfunction "(A12)PC4_39") (pintype "output"))
    )
    (net (code "111") (name "unconnected-(IC2-(IC1)PD4-Pad29)") (class "Default")
      (node (ref "IC2") (pin "29") (pinfunction "(IC1)PD4_29") (pintype "bidirectional"))
    )
    (net (code "112") (name "unconnected-(IC2-(MISO)PB3-Pad13)") (class "Default")
      (node (ref "IC2") (pin "13") (pinfunction "(MISO)PB3_13") (pintype "bidirectional"))
    )
    (net (code "113") (name "unconnected-(IC2-(T2)PD7-Pad32)") (class "Default")
      (node (ref "IC2") (pin "32") (pinfunction "(T2)PD7_32") (pintype "bidirectional"))
    )
    (net (code "114") (name "unconnected-(IC2-PEN-Pad1)") (class "Default")
      (node (ref "IC2") (pin "1") (pinfunction "PEN_1") (pintype "input"))
    )
    (net (code "115") (name "unconnected-(IC2-PF0(ADC0)-Pad61)") (class "Default")
      (node (ref "IC2") (pin "61") (pinfunction "PF0(ADC0)_61") (pintype "input"))
    )
    (net (code "116") (name "unconnected-(IC2-PF1(ADC1)-Pad60)") (class "Default")
      (node (ref "IC2") (pin "60") (pinfunction "PF1(ADC1)_60") (pintype "input"))
    )
    (net (code "117") (name "unconnected-(IC2-PG0(WR)-Pad33)") (class "Default")
      (node (ref "IC2") (pin "33") (pinfunction "PG0(WR)_33") (pintype "bidirectional"))
    )
    (net (code "118") (name "unconnected-(IC2-PG1(RD)-Pad34)") (class "Default")
      (node (ref "IC2") (pin "34") (pinfunction "PG1(RD)_34") (pintype "bidirectional"))
    )
    (net (code "119") (name "unconnected-(IC2-PG2(ALE)-Pad43)") (class "Default")
      (node (ref "IC2") (pin "43") (pinfunction "PG2(ALE)_43") (pintype "bidirectional"))
    )
    (net (code "120") (name "unconnected-(IC2-PG3(TOSC2)-Pad18)") (class "Default")
      (node (ref "IC2") (pin "18") (pinfunction "PG3(TOSC2)_18") (pintype "bidirectional"))
    )
    (net (code "121") (name "unconnected-(IC2-PG4(TOSC1)-Pad19)") (class "Default")
      (node (ref "IC2") (pin "19") (pinfunction "PG4(TOSC1)_19") (pintype "bidirectional"))
    )
    (net (code "122") (name "unconnected-(IC3-VREF-Pad5)") (class "Default")
      (node (ref "IC3") (pin "5") (pinfunction "VREF_5") (pintype "output"))
    )
    (net (code "123") (name "unconnected-(LED2-RED_A-Pad2)") (class "Default")
      (node (ref "LED2") (pin "2") (pinfunction "RED_A_2") (pintype "bidirectional"))
    )
    (net (code "124") (name "unconnected-(U$14-PadDIG7)") (class "Default")
      (node (ref "U$14") (pin "DIG7") (pinfunction "DIG7_DIG7") (pintype "bidirectional"))
    )
    (net (code "125") (name "unconnected-(U$14-PadDOUT)") (class "Default")
      (node (ref "U$14") (pin "DOUT") (pinfunction "DOUT_DOUT") (pintype "bidirectional"))
    )
  )
)
